# LCD_Rev-4.net
KiCad netlist of a schematic drawn in EAGLE
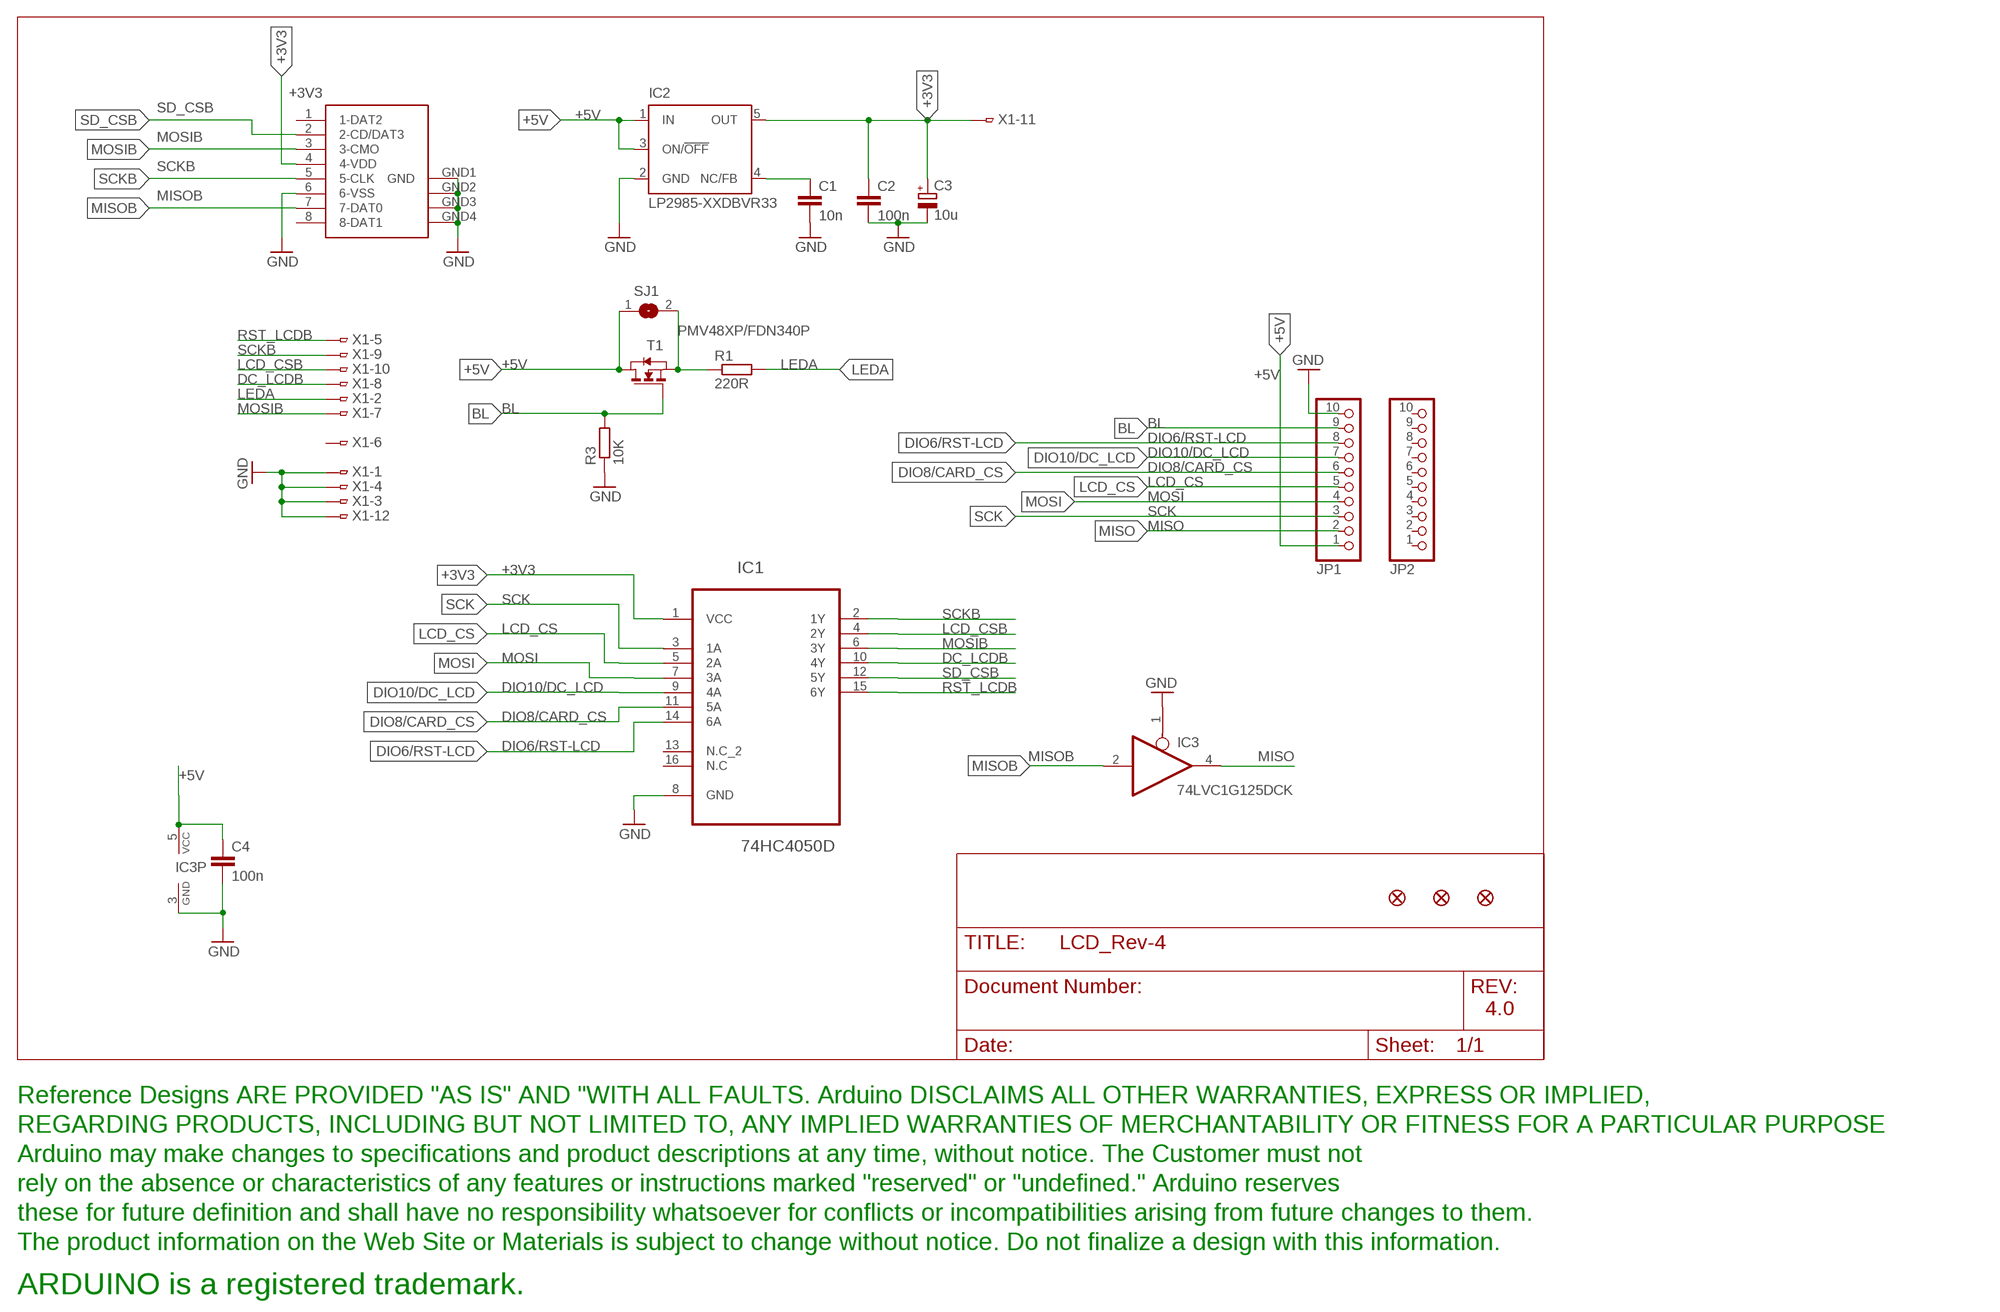
[diagram p0: schematic, sheet 1]

(export (version "E")
  (design (tool "Eeschema 10.0.6"))
  (components
    (comp (ref "C1")
      (value "10n")
      (footprint "eagle-import:C0603-ROUND")
      (libsource (lib "eagle-import") (part "C-EUC0603"))
    )
    (comp (ref "C2")
      (value "100n")
      (footprint "eagle-import:C0603-ROUND")
      (libsource (lib "eagle-import") (part "C-EUC0603"))
    )
    (comp (ref "C3")
      (value "10u")
      (footprint "eagle-import:SMC_B")
      (libsource (lib "eagle-import") (part "CPOL-EUSMCB"))
    )
    (comp (ref "C4")
      (value "100n")
      (footprint "eagle-import:C0603-ROUND")
      (libsource (lib "eagle-import") (part "C-EUC0603"))
    )
    (comp (ref "IC1")
      (value "74HC4050D")
      (footprint "eagle-import:SOIC127P600X175-16N")
      (libsource (lib "eagle-import") (part "74HC4050D"))
    )
    (comp (ref "IC2")
      (value "LP2985-XXDBVR33")
      (footprint "eagle-import:SOT23-DBV")
      (libsource (lib "eagle-import") (part "LP2985-XXDBVR33"))
    )
    (comp (ref "IC3")
      (value "74LVC1G125DCK")
      (footprint "eagle-import:SC70-5")
      (libsource (lib "eagle-import") (part "741G125DCKLVC"))
    )
    (comp (ref "JP1")
      (value "PINHD-1X10TH")
      (footprint "eagle-import:1X10-TH")
      (libsource (lib "eagle-import") (part "PINHD-1X10TH"))
    )
    (comp (ref "JP2")
      (value "PINHD-1X10TH")
      (footprint "eagle-import:1X10-TH")
      (libsource (lib "eagle-import") (part "PINHD-1X10TH"))
    )
    (comp (ref "R1")
      (value "220R")
      (footprint "eagle-import:R0603-ROUND")
      (libsource (lib "eagle-import") (part "R-EU_0603-RND"))
    )
    (comp (ref "R3")
      (value "10K")
      (footprint "eagle-import:R0603-ROUND")
      (libsource (lib "eagle-import") (part "R-EU_0603-RND"))
    )
    (comp (ref "SJ1")
      (value "SJL")
      (footprint "eagle-import:SJL")
      (libsource (lib "eagle-import") (part "SJL"))
    )
    (comp (ref "T1")
      (value "PMV48XP/FDN340P")
      (footprint "eagle-import:SOT-23")
      (libsource (lib "eagle-import") (part "NMOSSOT23"))
    )
    (comp (ref "U$1")
      (value "FIDUCIAL-LITTLE1X2")
      (footprint "eagle-import:FIDUCIAL-1X2")
      (libsource (lib "eagle-import") (part "FIDUCIAL-LITTLE1X2"))
    )
    (comp (ref "U$2")
      (value "DISCLAIMER")
      (footprint "eagle-import:DISCLAIMER")
      (libsource (lib "eagle-import") (part "DISCLAIMER"))
    )
    (comp (ref "U$3")
      (value "FIDUCIAL-LITTLE1X2")
      (footprint "eagle-import:FIDUCIAL-1X2")
      (libsource (lib "eagle-import") (part "FIDUCIAL-LITTLE1X2"))
    )
    (comp (ref "U$4")
      (value "FIDUCIAL-LITTLE1X2")
      (footprint "eagle-import:FIDUCIAL-1X2")
      (libsource (lib "eagle-import") (part "FIDUCIAL-LITTLE1X2"))
    )
    (comp (ref "U1")
      (value "SDCARD-15TW-8821")
      (footprint "eagle-import:SDCARD-15TW-8821")
      (libsource (lib "eagle-import") (part "SDCARD-15TW-8821"))
    )
    (comp (ref "X1")
      (value "FH12-12S-0.8SH")
      (footprint "eagle-import:FH12-12S-0.8SH")
      (fields (field (name "MPN") "MC34827"))
      (libsource (lib "eagle-import") (part "FH12-12S-0.8SH"))
    )
  )
  (nets
    (net (code "1") (name "+3V3") (class "Default")
      (node (ref "C2") (pin "1") (pinfunction "1_1") (pintype "passive"))
      (node (ref "C3") (pin "+") (pinfunction "+_+") (pintype "passive"))
      (node (ref "IC1") (pin "1") (pinfunction "VCC_1") (pintype "power_in"))
      (node (ref "IC2") (pin "5") (pinfunction "OUT_5") (pintype "passive"))
      (node (ref "U1") (pin "4") (pinfunction "4-VDD_4") (pintype "bidirectional"))
      (node (ref "X1") (pin "11") (pinfunction "1_11") (pintype "passive"))
    )
    (net (code "2") (name "+5V") (class "Default")
      (node (ref "C4") (pin "1") (pinfunction "1_1") (pintype "passive"))
      (node (ref "IC2") (pin "1") (pinfunction "IN_1") (pintype "input"))
      (node (ref "IC2") (pin "3") (pinfunction "ON/~{OFF}_3") (pintype "input"))
      (node (ref "IC3") (pin "5") (pinfunction "VCC_5") (pintype "power_in"))
      (node (ref "JP1") (pin "1") (pinfunction "1_1") (pintype "passive"))
      (node (ref "SJ1") (pin "1") (pinfunction "1_1") (pintype "passive"))
      (node (ref "T1") (pin "1") (pinfunction "D_1") (pintype "passive"))
    )
    (net (code "3") (name "/DC_LCDB") (class "Default")
      (node (ref "IC1") (pin "10") (pinfunction "4Y_10") (pintype "output"))
      (node (ref "X1") (pin "8") (pinfunction "1_8") (pintype "passive"))
    )
    (net (code "4") (name "/LCD_CSB") (class "Default")
      (node (ref "IC1") (pin "4") (pinfunction "2Y_4") (pintype "output"))
      (node (ref "X1") (pin "10") (pinfunction "1_10") (pintype "passive"))
    )
    (net (code "5") (name "/RST_LCDB") (class "Default")
      (node (ref "IC1") (pin "15") (pinfunction "6Y_15") (pintype "output"))
      (node (ref "X1") (pin "5") (pinfunction "1_5") (pintype "passive"))
    )
    (net (code "6") (name "BL") (class "Default")
      (node (ref "JP1") (pin "9") (pinfunction "9_9") (pintype "passive"))
      (node (ref "R3") (pin "2") (pinfunction "2_2") (pintype "passive"))
      (node (ref "T1") (pin "3") (pinfunction "G_3") (pintype "passive"))
    )
    (net (code "7") (name "DIO6{slash}RST-LCD") (class "Default")
      (node (ref "IC1") (pin "14") (pinfunction "6A_14") (pintype "input"))
      (node (ref "JP1") (pin "8") (pinfunction "8_8") (pintype "passive"))
    )
    (net (code "8") (name "DIO8{slash}CARD_CS") (class "Default")
      (node (ref "IC1") (pin "11") (pinfunction "5A_11") (pintype "input"))
      (node (ref "JP1") (pin "6") (pinfunction "6_6") (pintype "passive"))
    )
    (net (code "9") (name "DIO10{slash}DC_LCD") (class "Default")
      (node (ref "IC1") (pin "9") (pinfunction "4A_9") (pintype "input"))
      (node (ref "JP1") (pin "7") (pinfunction "7_7") (pintype "passive"))
    )
    (net (code "10") (name "GND") (class "Default")
      (node (ref "C1") (pin "2") (pinfunction "2_2") (pintype "passive"))
      (node (ref "C2") (pin "2") (pinfunction "2_2") (pintype "passive"))
      (node (ref "C3") (pin "-") (pinfunction "-_-") (pintype "passive"))
      (node (ref "C4") (pin "2") (pinfunction "2_2") (pintype "passive"))
      (node (ref "IC1") (pin "8") (pinfunction "GND_8") (pintype "passive"))
      (node (ref "IC2") (pin "2") (pinfunction "GND_2") (pintype "power_in"))
      (node (ref "IC3") (pin "1") (pinfunction "OE_1") (pintype "input"))
      (node (ref "IC3") (pin "3") (pinfunction "GND_3") (pintype "power_in"))
      (node (ref "JP1") (pin "10") (pinfunction "10_10") (pintype "passive"))
      (node (ref "R3") (pin "1") (pinfunction "1_1") (pintype "passive"))
      (node (ref "U1") (pin "6") (pinfunction "6-VSS_6") (pintype "bidirectional"))
      (node (ref "U1") (pin "GND1") (pinfunction "GND_GND1") (pintype "power_in"))
      (node (ref "U1") (pin "GND2") (pinfunction "GND1_GND2") (pintype "power_in"))
      (node (ref "U1") (pin "GND3") (pinfunction "GND2_GND3") (pintype "power_in"))
      (node (ref "U1") (pin "GND4") (pinfunction "GND3_GND4") (pintype "power_in"))
      (node (ref "X1") (pin "1") (pinfunction "1_1") (pintype "passive"))
      (node (ref "X1") (pin "12") (pinfunction "1_12") (pintype "passive"))
      (node (ref "X1") (pin "3") (pinfunction "1_3") (pintype "passive"))
      (node (ref "X1") (pin "4") (pinfunction "1_4") (pintype "passive"))
    )
    (net (code "11") (name "LCD_CS") (class "Default")
      (node (ref "IC1") (pin "5") (pinfunction "2A_5") (pintype "input"))
      (node (ref "JP1") (pin "5") (pinfunction "5_5") (pintype "passive"))
    )
    (net (code "12") (name "LEDA") (class "Default")
      (node (ref "R1") (pin "2") (pinfunction "2_2") (pintype "passive"))
      (node (ref "X1") (pin "2") (pinfunction "1_2") (pintype "passive"))
    )
    (net (code "13") (name "MISO") (class "Default")
      (node (ref "IC3") (pin "4") (pinfunction "O_4") (pintype "tri_state"))
      (node (ref "JP1") (pin "2") (pinfunction "2_2") (pintype "passive"))
    )
    (net (code "14") (name "MISOB") (class "Default")
      (node (ref "IC3") (pin "2") (pinfunction "I_2") (pintype "input"))
      (node (ref "U1") (pin "7") (pinfunction "7-DAT0_7") (pintype "bidirectional"))
    )
    (net (code "15") (name "MOSI") (class "Default")
      (node (ref "IC1") (pin "7") (pinfunction "3A_7") (pintype "input"))
      (node (ref "JP1") (pin "4") (pinfunction "4_4") (pintype "passive"))
    )
    (net (code "16") (name "MOSIB") (class "Default")
      (node (ref "IC1") (pin "6") (pinfunction "3Y_6") (pintype "output"))
      (node (ref "U1") (pin "3") (pinfunction "3-CMO_3") (pintype "bidirectional"))
      (node (ref "X1") (pin "7") (pinfunction "1_7") (pintype "passive"))
    )
    (net (code "17") (name "Net-(IC2-NC{slash}FB)") (class "Default")
      (node (ref "C1") (pin "1") (pinfunction "1_1") (pintype "passive"))
      (node (ref "IC2") (pin "4") (pinfunction "NC/FB_4") (pintype "passive"))
    )
    (net (code "18") (name "Net-(T1-S)") (class "Default")
      (node (ref "R1") (pin "1") (pinfunction "1_1") (pintype "passive"))
      (node (ref "SJ1") (pin "2") (pinfunction "2_2") (pintype "passive"))
      (node (ref "T1") (pin "2") (pinfunction "S_2") (pintype "passive"))
    )
    (net (code "19") (name "SCK") (class "Default")
      (node (ref "IC1") (pin "3") (pinfunction "1A_3") (pintype "input"))
      (node (ref "JP1") (pin "3") (pinfunction "3_3") (pintype "passive"))
    )
    (net (code "20") (name "SCKB") (class "Default")
      (node (ref "IC1") (pin "2") (pinfunction "1Y_2") (pintype "output"))
      (node (ref "U1") (pin "5") (pinfunction "5-CLK_5") (pintype "bidirectional"))
      (node (ref "X1") (pin "9") (pinfunction "1_9") (pintype "passive"))
    )
    (net (code "21") (name "SD_CSB") (class "Default")
      (node (ref "IC1") (pin "12") (pinfunction "5Y_12") (pintype "output"))
      (node (ref "U1") (pin "2") (pinfunction "2-CD/DAT3_2") (pintype "bidirectional"))
    )
    (net (code "22") (name "unconnected-(IC1-N.C-Pad16)") (class "Default")
      (node (ref "IC1") (pin "16") (pinfunction "N.C_16") (pintype "no_connect"))
    )
    (net (code "23") (name "unconnected-(IC1-N.C_2-Pad13)") (class "Default")
      (node (ref "IC1") (pin "13") (pinfunction "N.C_2_13") (pintype "no_connect"))
    )
    (net (code "24") (name "unconnected-(JP2-Pad1)") (class "Default")
      (node (ref "JP2") (pin "1") (pinfunction "1_1") (pintype "passive"))
    )
    (net (code "25") (name "unconnected-(JP2-Pad2)") (class "Default")
      (node (ref "JP2") (pin "2") (pinfunction "2_2") (pintype "passive"))
    )
    (net (code "26") (name "unconnected-(JP2-Pad3)") (class "Default")
      (node (ref "JP2") (pin "3") (pinfunction "3_3") (pintype "passive"))
    )
    (net (code "27") (name "unconnected-(JP2-Pad4)") (class "Default")
      (node (ref "JP2") (pin "4") (pinfunction "4_4") (pintype "passive"))
    )
    (net (code "28") (name "unconnected-(JP2-Pad5)") (class "Default")
      (node (ref "JP2") (pin "5") (pinfunction "5_5") (pintype "passive"))
    )
    (net (code "29") (name "unconnected-(JP2-Pad6)") (class "Default")
      (node (ref "JP2") (pin "6") (pinfunction "6_6") (pintype "passive"))
    )
    (net (code "30") (name "unconnected-(JP2-Pad7)") (class "Default")
      (node (ref "JP2") (pin "7") (pinfunction "7_7") (pintype "passive"))
    )
    (net (code "31") (name "unconnected-(JP2-Pad8)") (class "Default")
      (node (ref "JP2") (pin "8") (pinfunction "8_8") (pintype "passive"))
    )
    (net (code "32") (name "unconnected-(JP2-Pad9)") (class "Default")
      (node (ref "JP2") (pin "9") (pinfunction "9_9") (pintype "passive"))
    )
    (net (code "33") (name "unconnected-(JP2-Pad10)") (class "Default")
      (node (ref "JP2") (pin "10") (pinfunction "10_10") (pintype "passive"))
    )
    (net (code "34") (name "unconnected-(U1-1-DAT2-Pad1)") (class "Default")
      (node (ref "U1") (pin "1") (pinfunction "1-DAT2_1") (pintype "bidirectional"))
    )
    (net (code "35") (name "unconnected-(U1-8-DAT1-Pad8)") (class "Default")
      (node (ref "U1") (pin "8") (pinfunction "8-DAT1_8") (pintype "bidirectional"))
    )
    (net (code "36") (name "unconnected-(X1I-1-Pad6)") (class "Default")
      (node (ref "X1") (pin "6") (pinfunction "1_6") (pintype "passive"))
    )
  )
)
